# rn2xx3.net
KiCad netlist of a schematic drawn in EAGLE
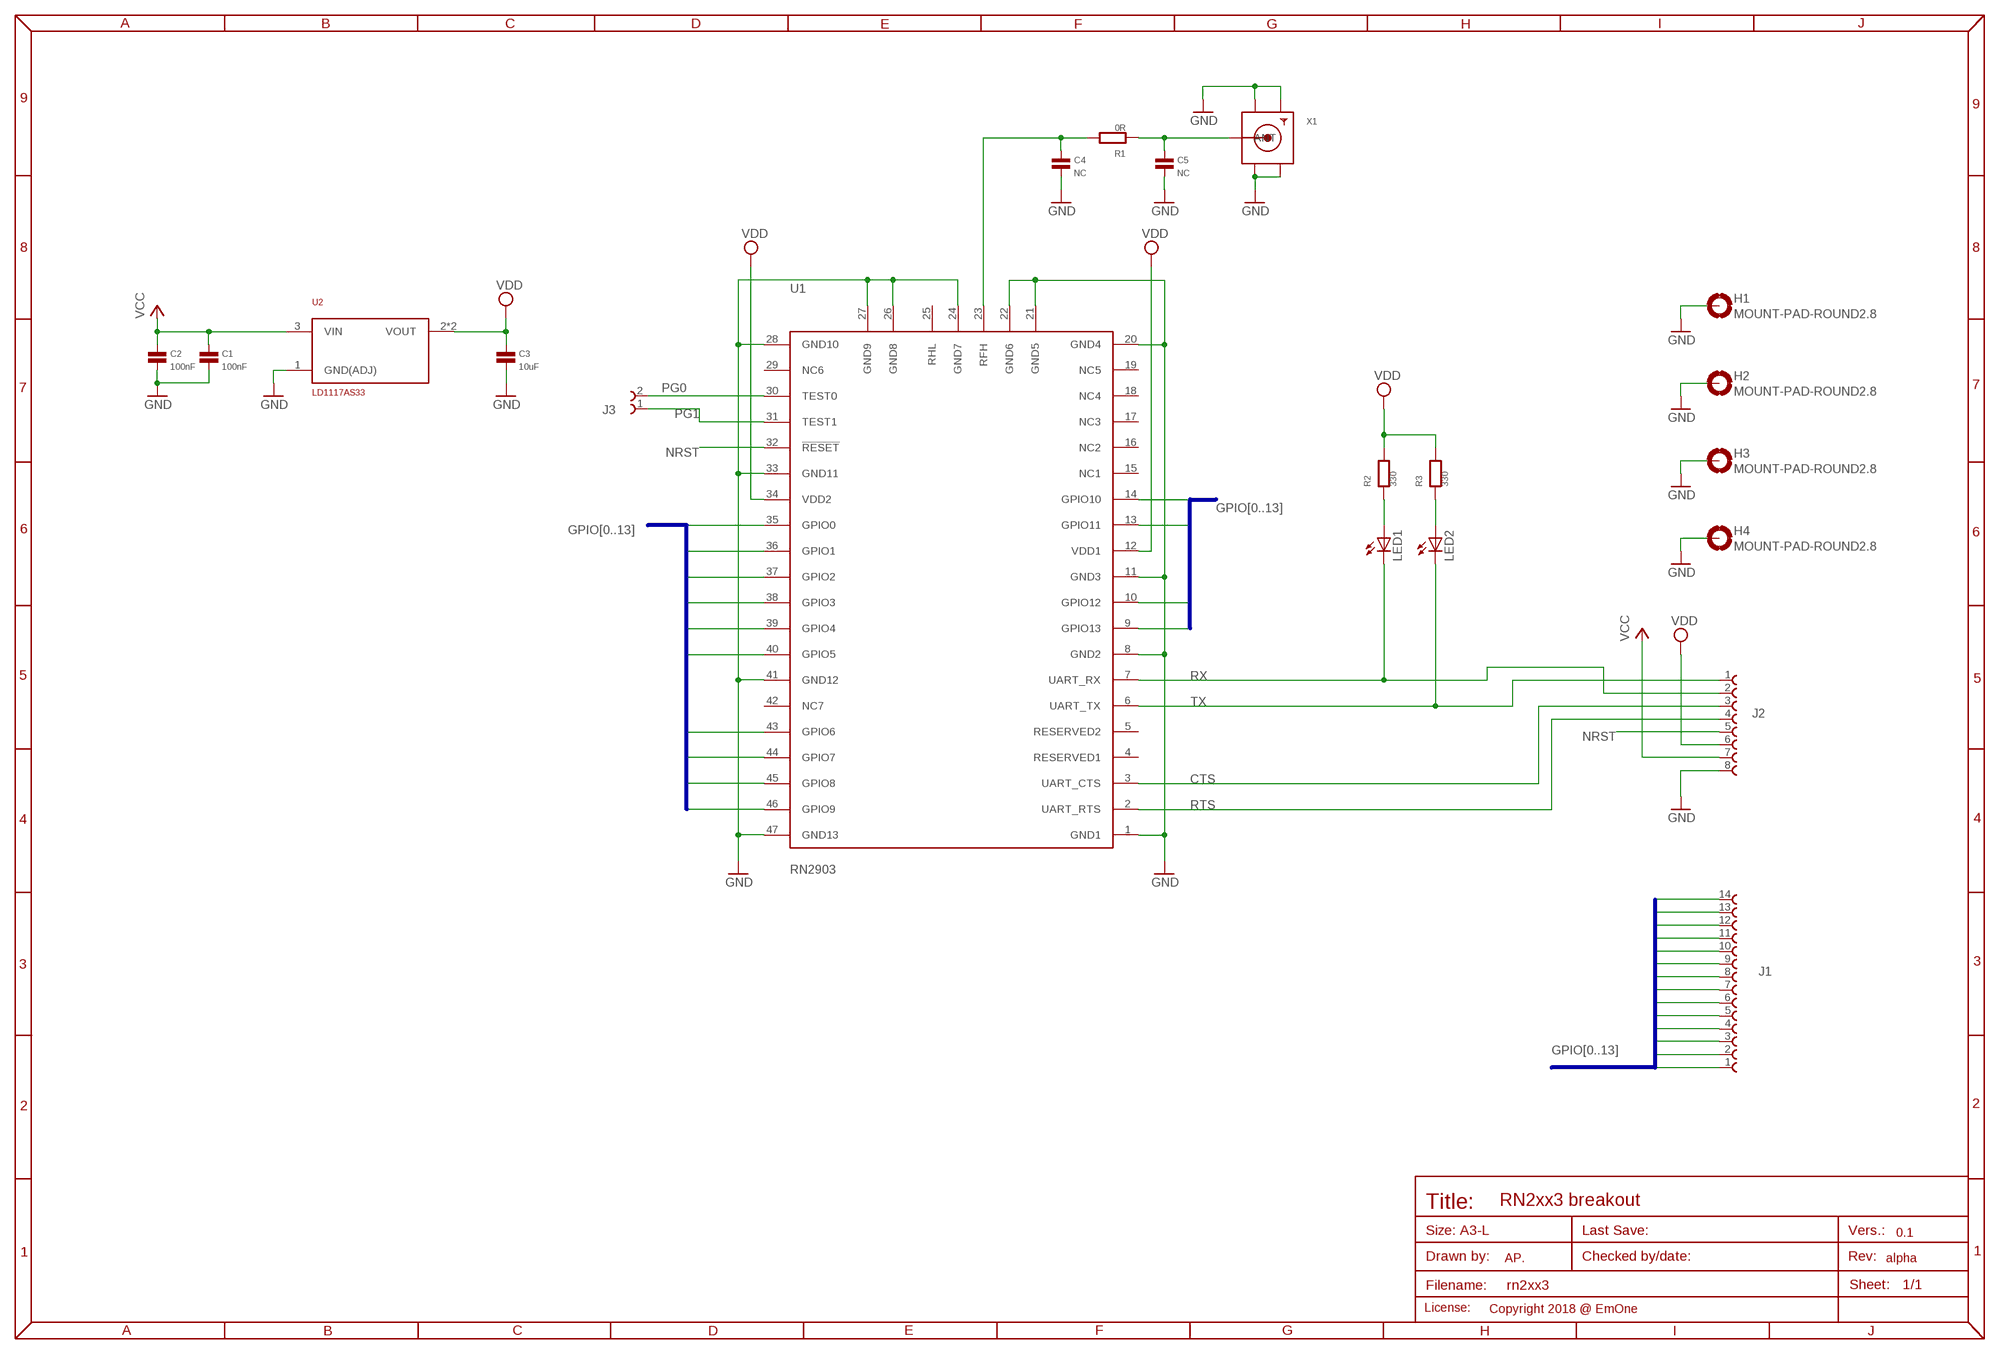
[diagram p0: schematic, sheet 1]

(export (version "E")
  (design (tool "Eeschema 10.0.6"))
  (components
    (comp (ref "C1")
      (value "100nF")
      (footprint "eagle-import:0603")
      (libsource (lib "eagle-import") (part "C0603"))
    )
    (comp (ref "C2")
      (value "100nF")
      (footprint "eagle-import:0603")
      (libsource (lib "eagle-import") (part "C0603"))
    )
    (comp (ref "C3")
      (value "10uF")
      (footprint "eagle-import:0603")
      (libsource (lib "eagle-import") (part "C0603"))
    )
    (comp (ref "C4")
      (value "NC")
      (footprint "eagle-import:0402")
      (libsource (lib "eagle-import") (part "C0402"))
    )
    (comp (ref "C5")
      (value "NC")
      (footprint "eagle-import:0402")
      (libsource (lib "eagle-import") (part "C0402"))
    )
    (comp (ref "H1")
      (value "MOUNT-PAD-ROUND2.8")
      (footprint "eagle-import:2,8-PAD")
      (libsource (lib "eagle-import") (part "MOUNT-PAD-ROUND2.8"))
    )
    (comp (ref "H2")
      (value "MOUNT-PAD-ROUND2.8")
      (footprint "eagle-import:2,8-PAD")
      (libsource (lib "eagle-import") (part "MOUNT-PAD-ROUND2.8"))
    )
    (comp (ref "H3")
      (value "MOUNT-PAD-ROUND2.8")
      (footprint "eagle-import:2,8-PAD")
      (libsource (lib "eagle-import") (part "MOUNT-PAD-ROUND2.8"))
    )
    (comp (ref "H4")
      (value "MOUNT-PAD-ROUND2.8")
      (footprint "eagle-import:2,8-PAD")
      (libsource (lib "eagle-import") (part "MOUNT-PAD-ROUND2.8"))
    )
    (comp (ref "J1")
      (value "61301411121")
      (footprint "eagle-import:61301411121")
      (libsource (lib "eagle-import") (part "61301411121"))
    )
    (comp (ref "J2")
      (value "61300811021")
      (footprint "eagle-import:61300811021")
      (libsource (lib "eagle-import") (part "61300811021"))
    )
    (comp (ref "J3")
      (value "61300211121")
      (footprint "eagle-import:61300211121")
      (libsource (lib "eagle-import") (part "61300211121"))
    )
    (comp (ref "LED1")
      (value "LED0603")
      (footprint "eagle-import:0603-LED")
      (libsource (lib "eagle-import") (part "LED0603"))
    )
    (comp (ref "LED2")
      (value "LED0603")
      (footprint "eagle-import:0603-LED")
      (libsource (lib "eagle-import") (part "LED0603"))
    )
    (comp (ref "R1")
      (value "0R")
      (footprint "eagle-import:0402")
      (libsource (lib "eagle-import") (part "R0402"))
    )
    (comp (ref "R2")
      (value "330")
      (footprint "eagle-import:0603")
      (libsource (lib "eagle-import") (part "R0603"))
    )
    (comp (ref "R3")
      (value "330")
      (footprint "eagle-import:0603")
      (libsource (lib "eagle-import") (part "R0603"))
    )
    (comp (ref "U1")
      (value "RN2903")
      (footprint "eagle-import:RN2483_RN2903")
      (libsource (lib "eagle-import") (part "RN2483/RN2903"))
    )
    (comp (ref "U2")
      (value "LD1117AS33")
      (footprint "eagle-import:SOT-223")
      (libsource (lib "eagle-import") (part "LD1117AS33"))
    )
    (comp (ref "X1")
      (value "SMACONNECTOR_EDGE_UFL")
      (footprint "eagle-import:SMA_EDGELAUNCH_UFL")
      (libsource (lib "eagle-import") (part "SMACONNECTOR_EDGE_UFL"))
    )
  )
  (nets
    (net (code "1") (name "/CTS") (class "Default")
      (node (ref "J2") (pin "3") (pinfunction "3_3") (pintype "passive"))
      (node (ref "U1") (pin "3") (pinfunction "UART_CTS_3") (pintype "bidirectional"))
    )
    (net (code "2") (name "/GPIO0") (class "Default")
      (node (ref "J1") (pin "1") (pinfunction "14_1") (pintype "passive"))
      (node (ref "U1") (pin "35") (pinfunction "GPIO0_35") (pintype "bidirectional"))
    )
    (net (code "3") (name "/GPIO1") (class "Default")
      (node (ref "J1") (pin "2") (pinfunction "13_2") (pintype "passive"))
      (node (ref "U1") (pin "36") (pinfunction "GPIO1_36") (pintype "bidirectional"))
    )
    (net (code "4") (name "/GPIO2") (class "Default")
      (node (ref "J1") (pin "3") (pinfunction "12_3") (pintype "passive"))
      (node (ref "U1") (pin "37") (pinfunction "GPIO2_37") (pintype "bidirectional"))
    )
    (net (code "5") (name "/GPIO3") (class "Default")
      (node (ref "J1") (pin "4") (pinfunction "11_4") (pintype "passive"))
      (node (ref "U1") (pin "38") (pinfunction "GPIO3_38") (pintype "bidirectional"))
    )
    (net (code "6") (name "/GPIO4") (class "Default")
      (node (ref "J1") (pin "5") (pinfunction "10_5") (pintype "passive"))
      (node (ref "U1") (pin "39") (pinfunction "GPIO4_39") (pintype "bidirectional"))
    )
    (net (code "7") (name "/GPIO5") (class "Default")
      (node (ref "J1") (pin "6") (pinfunction "9_6") (pintype "passive"))
      (node (ref "U1") (pin "40") (pinfunction "GPIO5_40") (pintype "bidirectional"))
    )
    (net (code "8") (name "/GPIO6") (class "Default")
      (node (ref "J1") (pin "7") (pinfunction "8_7") (pintype "passive"))
      (node (ref "U1") (pin "43") (pinfunction "GPIO6_43") (pintype "bidirectional"))
    )
    (net (code "9") (name "/GPIO7") (class "Default")
      (node (ref "J1") (pin "8") (pinfunction "7_8") (pintype "passive"))
      (node (ref "U1") (pin "44") (pinfunction "GPIO7_44") (pintype "bidirectional"))
    )
    (net (code "10") (name "/GPIO8") (class "Default")
      (node (ref "J1") (pin "9") (pinfunction "6_9") (pintype "passive"))
      (node (ref "U1") (pin "45") (pinfunction "GPIO8_45") (pintype "bidirectional"))
    )
    (net (code "11") (name "/GPIO9") (class "Default")
      (node (ref "J1") (pin "10") (pinfunction "5_10") (pintype "passive"))
      (node (ref "U1") (pin "46") (pinfunction "GPIO9_46") (pintype "bidirectional"))
    )
    (net (code "12") (name "/GPIO10") (class "Default")
      (node (ref "J1") (pin "11") (pinfunction "4_11") (pintype "passive"))
      (node (ref "U1") (pin "14") (pinfunction "GPIO10_14") (pintype "bidirectional"))
    )
    (net (code "13") (name "/GPIO11") (class "Default")
      (node (ref "J1") (pin "12") (pinfunction "3_12") (pintype "passive"))
      (node (ref "U1") (pin "13") (pinfunction "GPIO11_13") (pintype "bidirectional"))
    )
    (net (code "14") (name "/GPIO12") (class "Default")
      (node (ref "J1") (pin "13") (pinfunction "2_13") (pintype "passive"))
      (node (ref "U1") (pin "10") (pinfunction "GPIO12_10") (pintype "bidirectional"))
    )
    (net (code "15") (name "/GPIO13") (class "Default")
      (node (ref "J1") (pin "14") (pinfunction "1_14") (pintype "passive"))
      (node (ref "U1") (pin "9") (pinfunction "GPIO13_9") (pintype "bidirectional"))
    )
    (net (code "17") (name "/NRST") (class "Default")
      (node (ref "J2") (pin "5") (pinfunction "5_5") (pintype "passive"))
      (node (ref "U1") (pin "32") (pinfunction "~{RESET}_32") (pintype "bidirectional"))
    )
    (net (code "18") (name "/PG0") (class "Default")
      (node (ref "J3") (pin "2") (pinfunction "2_2") (pintype "passive"))
      (node (ref "U1") (pin "30") (pinfunction "TEST0_30") (pintype "bidirectional"))
    )
    (net (code "19") (name "/PG1") (class "Default")
      (node (ref "J3") (pin "1") (pinfunction "1_1") (pintype "passive"))
      (node (ref "U1") (pin "31") (pinfunction "TEST1_31") (pintype "bidirectional"))
    )
    (net (code "20") (name "/RTS") (class "Default")
      (node (ref "J2") (pin "4") (pinfunction "4_4") (pintype "passive"))
      (node (ref "U1") (pin "2") (pinfunction "UART_RTS_2") (pintype "bidirectional"))
    )
    (net (code "21") (name "/RX") (class "Default")
      (node (ref "J2") (pin "2") (pinfunction "2_2") (pintype "passive"))
      (node (ref "LED1") (pin "C") (pinfunction "C_C") (pintype "passive"))
      (node (ref "U1") (pin "7") (pinfunction "UART_RX_7") (pintype "bidirectional"))
    )
    (net (code "22") (name "/TX") (class "Default")
      (node (ref "J2") (pin "1") (pinfunction "1_1") (pintype "passive"))
      (node (ref "LED2") (pin "C") (pinfunction "C_C") (pintype "passive"))
      (node (ref "U1") (pin "6") (pinfunction "UART_TX_6") (pintype "bidirectional"))
    )
    (net (code "23") (name "GND") (class "Default")
      (node (ref "C1") (pin "2") (pinfunction "P$2_2") (pintype "passive"))
      (node (ref "C2") (pin "2") (pinfunction "P$2_2") (pintype "passive"))
      (node (ref "C3") (pin "2") (pinfunction "P$2_2") (pintype "passive"))
      (node (ref "C4") (pin "2") (pinfunction "P$2_2") (pintype "passive"))
      (node (ref "C5") (pin "2") (pinfunction "P$2_2") (pintype "passive"))
      (node (ref "H1") (pin "B2,8") (pinfunction "MOUNT_B2,8") (pintype "passive"))
      (node (ref "H2") (pin "B2,8") (pinfunction "MOUNT_B2,8") (pintype "passive"))
      (node (ref "H3") (pin "B2,8") (pinfunction "MOUNT_B2,8") (pintype "passive"))
      (node (ref "H4") (pin "B2,8") (pinfunction "MOUNT_B2,8") (pintype "passive"))
      (node (ref "J2") (pin "8") (pinfunction "8_8") (pintype "passive"))
      (node (ref "U1") (pin "1") (pinfunction "GND1_1") (pintype "bidirectional"))
      (node (ref "U1") (pin "11") (pinfunction "GND3_11") (pintype "bidirectional"))
      (node (ref "U1") (pin "20") (pinfunction "GND4_20") (pintype "bidirectional"))
      (node (ref "U1") (pin "21") (pinfunction "GND5_21") (pintype "bidirectional"))
      (node (ref "U1") (pin "22") (pinfunction "GND6_22") (pintype "bidirectional"))
      (node (ref "U1") (pin "24") (pinfunction "GND7_24") (pintype "bidirectional"))
      (node (ref "U1") (pin "26") (pinfunction "GND8_26") (pintype "bidirectional"))
      (node (ref "U1") (pin "27") (pinfunction "GND9_27") (pintype "bidirectional"))
      (node (ref "U1") (pin "28") (pinfunction "GND10_28") (pintype "bidirectional"))
      (node (ref "U1") (pin "33") (pinfunction "GND11_33") (pintype "bidirectional"))
      (node (ref "U1") (pin "41") (pinfunction "GND12_41") (pintype "bidirectional"))
      (node (ref "U1") (pin "47") (pinfunction "GND13_47") (pintype "bidirectional"))
      (node (ref "U1") (pin "8") (pinfunction "GND2_8") (pintype "bidirectional"))
      (node (ref "U2") (pin "1") (pinfunction "GND(ADJ)_1") (pintype "bidirectional"))
      (node (ref "X1") (pin "GND@1") (pinfunction "GND1_GND@1") (pintype "power_in"))
      (node (ref "X1") (pin "GND@2") (pinfunction "GND2_GND@2") (pintype "power_in"))
      (node (ref "X1") (pin "GND@3") (pinfunction "GND3_GND@3") (pintype "power_in"))
      (node (ref "X1") (pin "GND@4") (pinfunction "GND4_GND@4") (pintype "power_in"))
    )
    (net (code "24") (name "Net-(C4-P$1)") (class "Default")
      (node (ref "C4") (pin "1") (pinfunction "P$1_1") (pintype "passive"))
      (node (ref "R1") (pin "2") (pinfunction "P$2_2") (pintype "passive"))
      (node (ref "U1") (pin "23") (pinfunction "RFH_23") (pintype "bidirectional"))
    )
    (net (code "25") (name "Net-(C5-P$1)") (class "Default")
      (node (ref "C5") (pin "1") (pinfunction "P$1_1") (pintype "passive"))
      (node (ref "R1") (pin "1") (pinfunction "P$1_1") (pintype "passive"))
      (node (ref "X1") (pin "P") (pinfunction "ANT_P") (pintype "bidirectional"))
    )
    (net (code "26") (name "Net-(R2-P$1)") (class "Default")
      (node (ref "LED1") (pin "A") (pinfunction "A_A") (pintype "passive"))
      (node (ref "R2") (pin "1") (pinfunction "P$1_1") (pintype "passive"))
    )
    (net (code "27") (name "Net-(R3-P$1)") (class "Default")
      (node (ref "LED2") (pin "A") (pinfunction "A_A") (pintype "passive"))
      (node (ref "R3") (pin "1") (pinfunction "P$1_1") (pintype "passive"))
    )
    (net (code "28") (name "VCC") (class "Default")
      (node (ref "C1") (pin "1") (pinfunction "P$1_1") (pintype "passive"))
      (node (ref "C2") (pin "1") (pinfunction "P$1_1") (pintype "passive"))
      (node (ref "J2") (pin "7") (pinfunction "7_7") (pintype "passive"))
      (node (ref "U2") (pin "3") (pinfunction "VIN_3") (pintype "bidirectional"))
    )
    (net (code "29") (name "VDD") (class "Default")
      (node (ref "C3") (pin "1") (pinfunction "P$1_1") (pintype "passive"))
      (node (ref "J2") (pin "6") (pinfunction "6_6") (pintype "passive"))
      (node (ref "R2") (pin "2") (pinfunction "P$2_2") (pintype "passive"))
      (node (ref "R3") (pin "2") (pinfunction "P$2_2") (pintype "passive"))
      (node (ref "U1") (pin "12") (pinfunction "VDD1_12") (pintype "bidirectional"))
      (node (ref "U1") (pin "34") (pinfunction "VDD2_34") (pintype "bidirectional"))
      (node (ref "U2") (pin "2") (pinfunction "VOUT_2") (pintype "bidirectional"))
      (node (ref "U2") (pin "4") (pinfunction "VOUT_4") (pintype "bidirectional"))
    )
    (net (code "30") (name "unconnected-(U1-NC1-Pad15)") (class "Default")
      (node (ref "U1") (pin "15") (pinfunction "NC1_15") (pintype "bidirectional"))
    )
    (net (code "31") (name "unconnected-(U1-NC2-Pad16)") (class "Default")
      (node (ref "U1") (pin "16") (pinfunction "NC2_16") (pintype "bidirectional"))
    )
    (net (code "32") (name "unconnected-(U1-NC3-Pad17)") (class "Default")
      (node (ref "U1") (pin "17") (pinfunction "NC3_17") (pintype "bidirectional"))
    )
    (net (code "33") (name "unconnected-(U1-NC4-Pad18)") (class "Default")
      (node (ref "U1") (pin "18") (pinfunction "NC4_18") (pintype "bidirectional"))
    )
    (net (code "34") (name "unconnected-(U1-NC5-Pad19)") (class "Default")
      (node (ref "U1") (pin "19") (pinfunction "NC5_19") (pintype "bidirectional"))
    )
    (net (code "35") (name "unconnected-(U1-NC6-Pad29)") (class "Default")
      (node (ref "U1") (pin "29") (pinfunction "NC6_29") (pintype "bidirectional"))
    )
    (net (code "36") (name "unconnected-(U1-NC7-Pad42)") (class "Default")
      (node (ref "U1") (pin "42") (pinfunction "NC7_42") (pintype "bidirectional"))
    )
    (net (code "37") (name "unconnected-(U1-RESERVED1-Pad4)") (class "Default")
      (node (ref "U1") (pin "4") (pinfunction "RESERVED1_4") (pintype "bidirectional"))
    )
    (net (code "38") (name "unconnected-(U1-RESERVED2-Pad5)") (class "Default")
      (node (ref "U1") (pin "5") (pinfunction "RESERVED2_5") (pintype "bidirectional"))
    )
    (net (code "39") (name "unconnected-(U1-RHL-Pad25)") (class "Default")
      (node (ref "U1") (pin "25") (pinfunction "RHL_25") (pintype "bidirectional"))
    )
  )
)
